# AJH_as3340_20.net
KiCad netlist of a schematic drawn in EAGLE
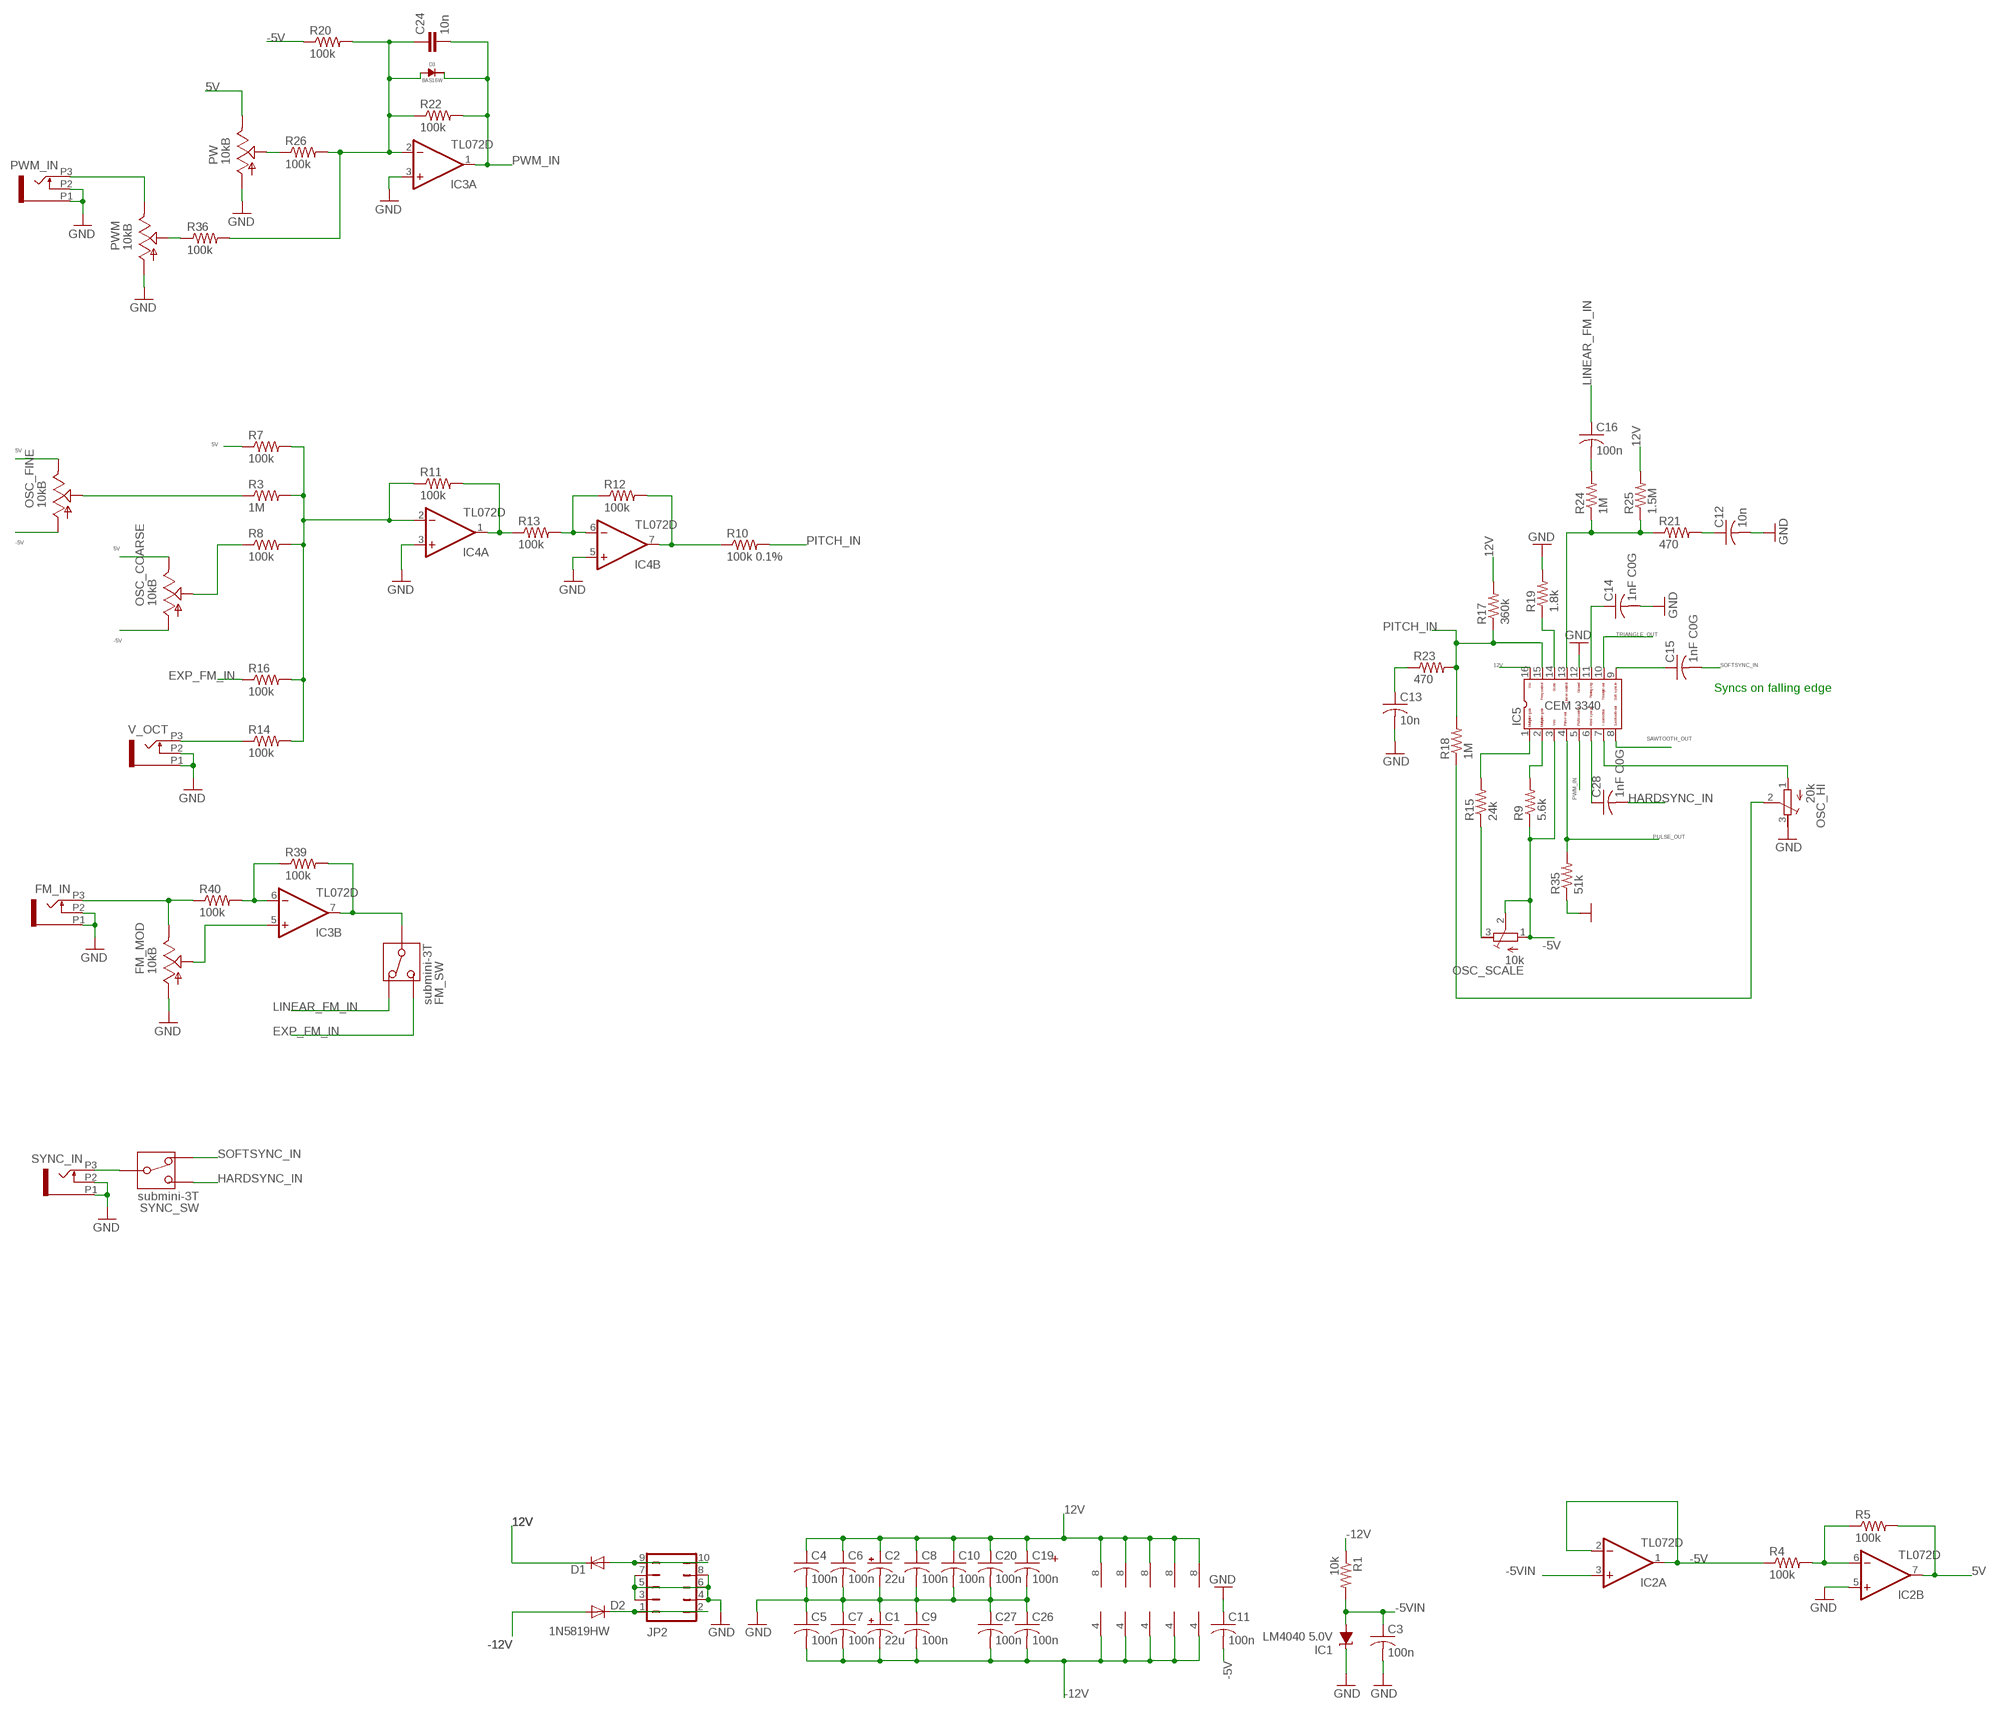
[diagram p0: schematic, sheet 1, part 1 of 2]
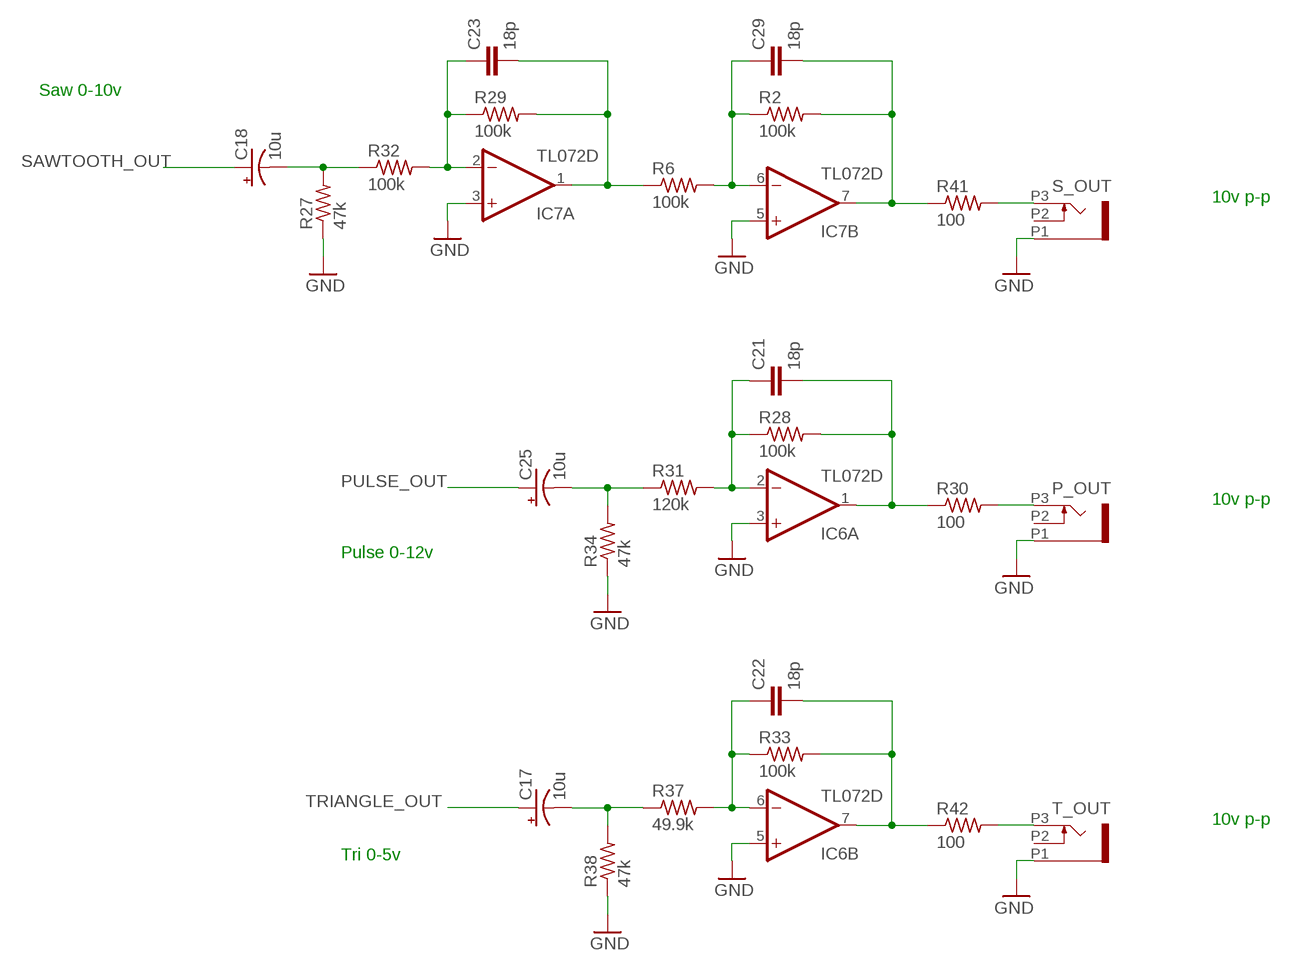
[diagram p1: schematic, sheet 1, part 2 of 2]

(export (version "E")
  (design (tool "Eeschema 10.0.6"))
  (components
    (comp (ref "C1")
      (value "22u")
      (footprint "eagle-import:PANASONIC_B")
      (libsource (lib "eagle-import") (part "CPOL-USB"))
    )
    (comp (ref "C2")
      (value "22u")
      (footprint "eagle-import:PANASONIC_B")
      (libsource (lib "eagle-import") (part "CPOL-USB"))
    )
    (comp (ref "C3")
      (value "100n")
      (footprint "eagle-import:C0603")
      (libsource (lib "eagle-import") (part "C-USC0603"))
    )
    (comp (ref "C4")
      (value "100n")
      (footprint "eagle-import:C0603")
      (libsource (lib "eagle-import") (part "C-USC0603"))
    )
    (comp (ref "C5")
      (value "100n")
      (footprint "eagle-import:C0603")
      (libsource (lib "eagle-import") (part "C-USC0603"))
    )
    (comp (ref "C6")
      (value "100n")
      (footprint "eagle-import:C0603")
      (libsource (lib "eagle-import") (part "C-USC0603"))
    )
    (comp (ref "C7")
      (value "100n")
      (footprint "eagle-import:C0603")
      (libsource (lib "eagle-import") (part "C-USC0603"))
    )
    (comp (ref "C8")
      (value "100n")
      (footprint "eagle-import:C0603")
      (libsource (lib "eagle-import") (part "C-USC0603"))
    )
    (comp (ref "C9")
      (value "100n")
      (footprint "eagle-import:C0603")
      (libsource (lib "eagle-import") (part "C-USC0603"))
    )
    (comp (ref "C10")
      (value "100n")
      (footprint "eagle-import:C0603")
      (libsource (lib "eagle-import") (part "C-USC0603"))
    )
    (comp (ref "C11")
      (value "100n")
      (footprint "eagle-import:C0603")
      (libsource (lib "eagle-import") (part "C-USC0603"))
    )
    (comp (ref "C12")
      (value "10n")
      (footprint "eagle-import:C0603")
      (libsource (lib "eagle-import") (part "C-USC0603"))
    )
    (comp (ref "C13")
      (value "10n")
      (footprint "eagle-import:C0603")
      (libsource (lib "eagle-import") (part "C-USC0603"))
    )
    (comp (ref "C14")
      (value "1nF C0G")
      (footprint "eagle-import:C0603")
      (libsource (lib "eagle-import") (part "C-USC0603"))
    )
    (comp (ref "C15")
      (value "1nF C0G")
      (footprint "eagle-import:C0603")
      (libsource (lib "eagle-import") (part "C-USC0603"))
    )
    (comp (ref "C16")
      (value "100n")
      (footprint "eagle-import:C0603")
      (libsource (lib "eagle-import") (part "C-USC0603"))
    )
    (comp (ref "C17")
      (value "10u")
      (footprint "eagle-import:PANASONIC_B")
      (libsource (lib "eagle-import") (part "CPOL-USB"))
    )
    (comp (ref "C18")
      (value "10u")
      (footprint "eagle-import:PANASONIC_B")
      (libsource (lib "eagle-import") (part "CPOL-USB"))
    )
    (comp (ref "C19")
      (value "100n")
      (footprint "eagle-import:C0603")
      (libsource (lib "eagle-import") (part "C-USC0603"))
    )
    (comp (ref "C20")
      (value "100n")
      (footprint "eagle-import:C0603")
      (libsource (lib "eagle-import") (part "C-USC0603"))
    )
    (comp (ref "C21")
      (value "18p")
      (footprint "eagle-import:C0603")
      (libsource (lib "eagle-import") (part "C-EUC0603"))
    )
    (comp (ref "C22")
      (value "18p")
      (footprint "eagle-import:C0603")
      (libsource (lib "eagle-import") (part "C-EUC0603"))
    )
    (comp (ref "C23")
      (value "18p")
      (footprint "eagle-import:C0603")
      (libsource (lib "eagle-import") (part "C-EUC0603"))
    )
    (comp (ref "C24")
      (value "10n")
      (footprint "eagle-import:C0603")
      (libsource (lib "eagle-import") (part "C-EUC0603"))
    )
    (comp (ref "C25")
      (value "10u")
      (footprint "eagle-import:PANASONIC_B")
      (libsource (lib "eagle-import") (part "CPOL-USB"))
    )
    (comp (ref "C26")
      (value "100n")
      (footprint "eagle-import:C0603")
      (libsource (lib "eagle-import") (part "C-USC0603"))
    )
    (comp (ref "C27")
      (value "100n")
      (footprint "eagle-import:C0603")
      (libsource (lib "eagle-import") (part "C-USC0603"))
    )
    (comp (ref "C28")
      (value "1nF C0G")
      (footprint "eagle-import:C0603")
      (libsource (lib "eagle-import") (part "C-USC0603"))
    )
    (comp (ref "C29")
      (value "18p")
      (footprint "eagle-import:C0603")
      (libsource (lib "eagle-import") (part "C-EUC0603"))
    )
    (comp (ref "D1")
      (value "1N5819HW")
      (footprint "eagle-import:SOD123")
      (libsource (lib "eagle-import") (part "DIODE-SOD123"))
    )
    (comp (ref "D2")
      (value "1N5819HW")
      (footprint "eagle-import:SOD123")
      (libsource (lib "eagle-import") (part "DIODE-SOD123"))
    )
    (comp (ref "D3")
      (value "BAS16W")
      (footprint "eagle-import:SOT-323")
      (libsource (lib "eagle-import") (part "BAS16W"))
    )
    (comp (ref "FM_IN")
      (value "PJ301_THONKICONN6")
      (footprint "eagle-import:WQP_PJ_301M6")
      (libsource (lib "eagle-import") (part "PJ301_THONKICONN6"))
    )
    (comp (ref "FM_MOD")
      (value "10kB")
      (footprint "eagle-import:ALPS_POT_VERTICAL_PS")
      (libsource (lib "eagle-import") (part "pot-alps_POT_USVERTICAL_PS"))
    )
    (comp (ref "FM_SW")
      (value "submini-3T")
      (footprint "eagle-import:SPDT-SUB")
      (libsource (lib "eagle-import") (part "SPDTT"))
    )
    (comp (ref "IC1")
      (value "LM4040 5.0V")
      (footprint "eagle-import:DBZ_R-PDSO-G3")
      (libsource (lib "eagle-import") (part "LM4041DBZC12"))
    )
    (comp (ref "IC2")
      (value "TL072D")
      (footprint "eagle-import:SO08")
      (libsource (lib "eagle-import") (part "TL072D"))
    )
    (comp (ref "IC3")
      (value "TL072D")
      (footprint "eagle-import:SO08")
      (libsource (lib "eagle-import") (part "TL072D"))
    )
    (comp (ref "IC4")
      (value "TL072D")
      (footprint "eagle-import:SO08")
      (libsource (lib "eagle-import") (part "TL072D"))
    )
    (comp (ref "IC5")
      (value "CEM3340SOIC16")
      (footprint "eagle-import:SO16")
      (libsource (lib "eagle-import") (part "CEM3340SOIC16"))
    )
    (comp (ref "IC6")
      (value "TL072D")
      (footprint "eagle-import:SO08")
      (libsource (lib "eagle-import") (part "TL072D"))
    )
    (comp (ref "IC7")
      (value "TL072D")
      (footprint "eagle-import:SO08")
      (libsource (lib "eagle-import") (part "TL072D"))
    )
    (comp (ref "JP2")
      (value "JP5Q")
      (footprint "eagle-import:JP5Q")
      (libsource (lib "eagle-import") (part "JP5Q"))
    )
    (comp (ref "OSC_COARSE")
      (value "10kB")
      (footprint "eagle-import:ALPS_POT_VERTICAL")
      (libsource (lib "eagle-import") (part "POT_USVERTICAL"))
    )
    (comp (ref "OSC_FINE")
      (value "10kB")
      (footprint "eagle-import:ALPS_POT_VERTICAL")
      (libsource (lib "eagle-import") (part "POT_USVERTICAL"))
    )
    (comp (ref "OSC_HI")
      (value "20k")
      (footprint "eagle-import:RTRIM3296X")
      (libsource (lib "eagle-import") (part "R-TRIMM3296X"))
    )
    (comp (ref "OSC_SCALE")
      (value "10k")
      (footprint "eagle-import:RTRIM3296X")
      (libsource (lib "eagle-import") (part "R-TRIMM3296X"))
    )
    (comp (ref "PW")
      (value "10kB")
      (footprint "eagle-import:ALPS_POT_VERTICAL_PS")
      (libsource (lib "eagle-import") (part "pot-alps_POT_USVERTICAL_PS"))
    )
    (comp (ref "PWM")
      (value "10kB")
      (footprint "eagle-import:ALPS_POT_VERTICAL_PS")
      (libsource (lib "eagle-import") (part "pot-alps_POT_USVERTICAL_PS"))
    )
    (comp (ref "PWM_IN")
      (value "PJ301_THONKICONN6")
      (footprint "eagle-import:WQP_PJ_301M6")
      (libsource (lib "eagle-import") (part "PJ301_THONKICONN6"))
    )
    (comp (ref "P_OUT")
      (value "PJ301_THONKICONN6")
      (footprint "eagle-import:WQP_PJ_301M6")
      (libsource (lib "eagle-import") (part "PJ301_THONKICONN6"))
    )
    (comp (ref "R1")
      (value "10k")
      (footprint "eagle-import:R0603")
      (libsource (lib "eagle-import") (part "R-US_R0603"))
    )
    (comp (ref "R2")
      (value "100k")
      (footprint "eagle-import:R0603")
      (libsource (lib "eagle-import") (part "R-US_R0603"))
    )
    (comp (ref "R3")
      (value "1M")
      (footprint "eagle-import:R0603")
      (libsource (lib "eagle-import") (part "R-US_R0603"))
    )
    (comp (ref "R4")
      (value "100k")
      (footprint "eagle-import:R0603")
      (libsource (lib "eagle-import") (part "R-US_R0603"))
    )
    (comp (ref "R5")
      (value "100k")
      (footprint "eagle-import:R0603")
      (libsource (lib "eagle-import") (part "R-US_R0603"))
    )
    (comp (ref "R6")
      (value "100k")
      (footprint "eagle-import:R0603")
      (libsource (lib "eagle-import") (part "R-US_R0603"))
    )
    (comp (ref "R7")
      (value "100k")
      (footprint "eagle-import:R0603")
      (libsource (lib "eagle-import") (part "R-US_R0603"))
    )
    (comp (ref "R8")
      (value "100k")
      (footprint "eagle-import:R0603")
      (libsource (lib "eagle-import") (part "R-US_R0603"))
    )
    (comp (ref "R9")
      (value "5.6k")
      (footprint "eagle-import:R0603")
      (libsource (lib "eagle-import") (part "R-US_R0603"))
    )
    (comp (ref "R10")
      (value "100k 0.1%")
      (footprint "eagle-import:R0603")
      (libsource (lib "eagle-import") (part "R-US_R0603"))
    )
    (comp (ref "R11")
      (value "100k")
      (footprint "eagle-import:R0603")
      (libsource (lib "eagle-import") (part "R-US_R0603"))
    )
    (comp (ref "R12")
      (value "100k")
      (footprint "eagle-import:R0603")
      (libsource (lib "eagle-import") (part "R-US_R0603"))
    )
    (comp (ref "R13")
      (value "100k")
      (footprint "eagle-import:R0603")
      (libsource (lib "eagle-import") (part "R-US_R0603"))
    )
    (comp (ref "R14")
      (value "100k")
      (footprint "eagle-import:R0603")
      (libsource (lib "eagle-import") (part "R-US_R0603"))
    )
    (comp (ref "R15")
      (value "24k")
      (footprint "eagle-import:R0603")
      (libsource (lib "eagle-import") (part "R-US_R0603"))
    )
    (comp (ref "R16")
      (value "100k")
      (footprint "eagle-import:R0603")
      (libsource (lib "eagle-import") (part "R-US_R0603"))
    )
    (comp (ref "R17")
      (value "360k")
      (footprint "eagle-import:R0603")
      (libsource (lib "eagle-import") (part "R-US_R0603"))
    )
    (comp (ref "R18")
      (value "1M")
      (footprint "eagle-import:R0603")
      (libsource (lib "eagle-import") (part "R-US_R0603"))
    )
    (comp (ref "R19")
      (value "1.8k")
      (footprint "eagle-import:R0603")
      (libsource (lib "eagle-import") (part "R-US_R0603"))
    )
    (comp (ref "R20")
      (value "100k")
      (footprint "eagle-import:R0603")
      (libsource (lib "eagle-import") (part "R-US_R0603"))
    )
    (comp (ref "R21")
      (value "470")
      (footprint "eagle-import:R0603")
      (libsource (lib "eagle-import") (part "R-US_R0603"))
    )
    (comp (ref "R22")
      (value "100k")
      (footprint "eagle-import:R0603")
      (libsource (lib "eagle-import") (part "R-US_R0603"))
    )
    (comp (ref "R23")
      (value "470")
      (footprint "eagle-import:R0603")
      (libsource (lib "eagle-import") (part "R-US_R0603"))
    )
    (comp (ref "R24")
      (value "1M")
      (footprint "eagle-import:R0603")
      (libsource (lib "eagle-import") (part "R-US_R0603"))
    )
    (comp (ref "R25")
      (value "1.5M")
      (footprint "eagle-import:R0603")
      (libsource (lib "eagle-import") (part "R-US_R0603"))
    )
    (comp (ref "R26")
      (value "100k")
      (footprint "eagle-import:R0603")
      (libsource (lib "eagle-import") (part "R-US_R0603"))
    )
    (comp (ref "R27")
      (value "47k")
      (footprint "eagle-import:R0603")
      (libsource (lib "eagle-import") (part "R-US_R0603"))
    )
    (comp (ref "R28")
      (value "100k")
      (footprint "eagle-import:R0603")
      (libsource (lib "eagle-import") (part "R-US_R0603"))
    )
    (comp (ref "R29")
      (value "100k")
      (footprint "eagle-import:R0603")
      (libsource (lib "eagle-import") (part "R-US_R0603"))
    )
    (comp (ref "R30")
      (value "100")
      (footprint "eagle-import:R0603")
      (libsource (lib "eagle-import") (part "R-US_R0603"))
    )
    (comp (ref "R31")
      (value "120k")
      (footprint "eagle-import:R0603")
      (libsource (lib "eagle-import") (part "R-US_R0603"))
    )
    (comp (ref "R32")
      (value "100k")
      (footprint "eagle-import:R0603")
      (libsource (lib "eagle-import") (part "R-US_R0603"))
    )
    (comp (ref "R33")
      (value "100k")
      (footprint "eagle-import:R0603")
      (libsource (lib "eagle-import") (part "R-US_R0603"))
    )
    (comp (ref "R34")
      (value "47k")
      (footprint "eagle-import:R0603")
      (libsource (lib "eagle-import") (part "R-US_R0603"))
    )
    (comp (ref "R35")
      (value "51k")
      (footprint "eagle-import:R0603")
      (libsource (lib "eagle-import") (part "R-US_R0603"))
    )
    (comp (ref "R36")
      (value "100k")
      (footprint "eagle-import:R0603")
      (libsource (lib "eagle-import") (part "R-US_R0603"))
    )
    (comp (ref "R37")
      (value "49.9k")
      (footprint "eagle-import:R0603")
      (libsource (lib "eagle-import") (part "R-US_R0603"))
    )
    (comp (ref "R38")
      (value "47k")
      (footprint "eagle-import:R0603")
      (libsource (lib "eagle-import") (part "R-US_R0603"))
    )
    (comp (ref "R39")
      (value "100k")
      (footprint "eagle-import:R0603")
      (libsource (lib "eagle-import") (part "R-US_R0603"))
    )
    (comp (ref "R40")
      (value "100k")
      (footprint "eagle-import:R0603")
      (libsource (lib "eagle-import") (part "R-US_R0603"))
    )
    (comp (ref "R41")
      (value "100")
      (footprint "eagle-import:R0603")
      (libsource (lib "eagle-import") (part "R-US_R0603"))
    )
    (comp (ref "R42")
      (value "100")
      (footprint "eagle-import:R0603")
      (libsource (lib "eagle-import") (part "R-US_R0603"))
    )
    (comp (ref "SYNC_IN")
      (value "PJ301_THONKICONN6")
      (footprint "eagle-import:WQP_PJ_301M6")
      (libsource (lib "eagle-import") (part "PJ301_THONKICONN6"))
    )
    (comp (ref "SYNC_SW")
      (value "submini-3T")
      (footprint "eagle-import:SPDT-SUB")
      (libsource (lib "eagle-import") (part "SPDTT"))
    )
    (comp (ref "S_OUT")
      (value "PJ301_THONKICONN6")
      (footprint "eagle-import:WQP_PJ_301M6")
      (libsource (lib "eagle-import") (part "PJ301_THONKICONN6"))
    )
    (comp (ref "T_OUT")
      (value "PJ301_THONKICONN6")
      (footprint "eagle-import:WQP_PJ_301M6")
      (libsource (lib "eagle-import") (part "PJ301_THONKICONN6"))
    )
    (comp (ref "V_OCT")
      (value "PJ301_THONKICONN6")
      (footprint "eagle-import:WQP_PJ_301M6")
      (libsource (lib "eagle-import") (part "PJ301_THONKICONN6"))
    )
  )
  (nets
    (net (code "1") (name "/-5V") (class "Default")
      (node (ref "C11") (pin "2") (pinfunction "2_2") (pintype "passive"))
      (node (ref "IC2") (pin "1") (pinfunction "OUT_1") (pintype "output"))
      (node (ref "IC2") (pin "2") (pinfunction "-IN_2") (pintype "input"))
      (node (ref "IC5") (pin "3") (pinfunction "3_3") (pintype "power_in"))
      (node (ref "OSC_COARSE") (pin "P$3") (pinfunction "A_P$3") (pintype "passive"))
      (node (ref "OSC_FINE") (pin "P$3") (pinfunction "A_P$3") (pintype "passive"))
      (node (ref "OSC_SCALE") (pin "1") (pinfunction "E_1") (pintype "passive"))
      (node (ref "OSC_SCALE") (pin "2") (pinfunction "S_2") (pintype "passive"))
      (node (ref "R20") (pin "1") (pinfunction "1_1") (pintype "passive"))
      (node (ref "R4") (pin "1") (pinfunction "1_1") (pintype "passive"))
      (node (ref "R9") (pin "1") (pinfunction "1_1") (pintype "passive"))
    )
    (net (code "2") (name "/-5VIN") (class "Default")
      (node (ref "C3") (pin "1") (pinfunction "1_1") (pintype "passive"))
      (node (ref "IC1") (pin "2") (pinfunction "A_2") (pintype "passive"))
      (node (ref "IC2") (pin "3") (pinfunction "+IN_3") (pintype "input"))
      (node (ref "R1") (pin "2") (pinfunction "2_2") (pintype "passive"))
    )
    (net (code "3") (name "/-12V") (class "Default")
      (node (ref "C1") (pin "-") (pinfunction "-_-") (pintype "passive"))
      (node (ref "C26") (pin "2") (pinfunction "2_2") (pintype "passive"))
      (node (ref "C27") (pin "2") (pinfunction "2_2") (pintype "passive"))
      (node (ref "C5") (pin "2") (pinfunction "2_2") (pintype "passive"))
      (node (ref "C7") (pin "2") (pinfunction "2_2") (pintype "passive"))
      (node (ref "C9") (pin "2") (pinfunction "2_2") (pintype "passive"))
      (node (ref "D2") (pin "A") (pinfunction "A_A") (pintype "passive"))
      (node (ref "IC2") (pin "4") (pinfunction "V-_4") (pintype "power_in"))
      (node (ref "IC3") (pin "4") (pinfunction "V-_4") (pintype "power_in"))
      (node (ref "IC4") (pin "4") (pinfunction "V-_4") (pintype "power_in"))
      (node (ref "IC6") (pin "4") (pinfunction "V-_4") (pintype "power_in"))
      (node (ref "IC7") (pin "4") (pinfunction "V-_4") (pintype "power_in"))
      (node (ref "R1") (pin "1") (pinfunction "1_1") (pintype "passive"))
    )
    (net (code "4") (name "/5V") (class "Default")
      (node (ref "IC2") (pin "7") (pinfunction "OUT_7") (pintype "output"))
      (node (ref "OSC_COARSE") (pin "P$1") (pinfunction "E_P$1") (pintype "passive"))
      (node (ref "OSC_FINE") (pin "P$1") (pinfunction "E_P$1") (pintype "passive"))
      (node (ref "PW") (pin "P$1") (pinfunction "E_P$1") (pintype "passive"))
      (node (ref "R5") (pin "2") (pinfunction "2_2") (pintype "passive"))
      (node (ref "R7") (pin "1") (pinfunction "1_1") (pintype "passive"))
    )
    (net (code "5") (name "/12V") (class "Default")
      (node (ref "C10") (pin "1") (pinfunction "1_1") (pintype "passive"))
      (node (ref "C19") (pin "1") (pinfunction "1_1") (pintype "passive"))
      (node (ref "C2") (pin "+") (pinfunction "+_+") (pintype "passive"))
      (node (ref "C20") (pin "1") (pinfunction "1_1") (pintype "passive"))
      (node (ref "C4") (pin "1") (pinfunction "1_1") (pintype "passive"))
      (node (ref "C6") (pin "1") (pinfunction "1_1") (pintype "passive"))
      (node (ref "C8") (pin "1") (pinfunction "1_1") (pintype "passive"))
      (node (ref "D1") (pin "C") (pinfunction "C_C") (pintype "passive"))
      (node (ref "IC2") (pin "8") (pinfunction "V+_8") (pintype "power_in"))
      (node (ref "IC3") (pin "8") (pinfunction "V+_8") (pintype "power_in"))
      (node (ref "IC4") (pin "8") (pinfunction "V+_8") (pintype "power_in"))
      (node (ref "IC5") (pin "16") (pinfunction "16_16") (pintype "power_in"))
      (node (ref "IC6") (pin "8") (pinfunction "V+_8") (pintype "power_in"))
      (node (ref "IC7") (pin "8") (pinfunction "V+_8") (pintype "power_in"))
      (node (ref "R17") (pin "2") (pinfunction "2_2") (pintype "passive"))
      (node (ref "R25") (pin "2") (pinfunction "2_2") (pintype "passive"))
    )
    (net (code "6") (name "/EXP_FM_IN") (class "Default")
      (node (ref "FM_SW") (pin "P$1") (pinfunction "P$1_P$1") (pintype "passive"))
      (node (ref "R16") (pin "1") (pinfunction "1_1") (pintype "passive"))
    )
    (net (code "7") (name "/HARDSYNC_IN") (class "Default")
      (node (ref "C28") (pin "2") (pinfunction "2_2") (pintype "passive"))
      (node (ref "SYNC_SW") (pin "P$1") (pinfunction "P$1_P$1") (pintype "passive"))
    )
    (net (code "8") (name "/LINEAR_FM_IN") (class "Default")
      (node (ref "C16") (pin "1") (pinfunction "1_1") (pintype "passive"))
      (node (ref "FM_SW") (pin "P$3") (pinfunction "P$3_P$3") (pintype "passive"))
    )
    (net (code "9") (name "/PITCH_IN") (class "Default")
      (node (ref "IC5") (pin "15") (pinfunction "15_15") (pintype "input"))
      (node (ref "R10") (pin "2") (pinfunction "2_2") (pintype "passive"))
      (node (ref "R17") (pin "1") (pinfunction "1_1") (pintype "passive"))
      (node (ref "R18") (pin "2") (pinfunction "2_2") (pintype "passive"))
      (node (ref "R23") (pin "2") (pinfunction "2_2") (pintype "passive"))
    )
    (net (code "10") (name "/PULSE_OUT") (class "Default")
      (node (ref "C25") (pin "+") (pinfunction "+_+") (pintype "passive"))
      (node (ref "IC5") (pin "4") (pinfunction "4_4") (pintype "output"))
      (node (ref "R35") (pin "2") (pinfunction "2_2") (pintype "passive"))
    )
    (net (code "11") (name "/PWM_IN") (class "Default")
      (node (ref "C24") (pin "2") (pinfunction "2_2") (pintype "passive"))
      (node (ref "D3") (pin "CATHODE") (pinfunction "CATHODE_CATHODE") (pintype "bidirectional"))
      (node (ref "IC3") (pin "1") (pinfunction "OUT_1") (pintype "output"))
      (node (ref "IC5") (pin "5") (pinfunction "5_5") (pintype "input"))
      (node (ref "R22") (pin "2") (pinfunction "2_2") (pintype "passive"))
    )
    (net (code "12") (name "/SAWTOOTH_OUT") (class "Default")
      (node (ref "C18") (pin "+") (pinfunction "+_+") (pintype "passive"))
      (node (ref "IC5") (pin "8") (pinfunction "8_8") (pintype "output"))
    )
    (net (code "13") (name "/SOFTSYNC_IN") (class "Default")
      (node (ref "C15") (pin "2") (pinfunction "2_2") (pintype "passive"))
      (node (ref "SYNC_SW") (pin "P$3") (pinfunction "P$3_P$3") (pintype "passive"))
    )
    (net (code "14") (name "/TRIANGLE_OUT") (class "Default")
      (node (ref "C17") (pin "+") (pinfunction "+_+") (pintype "passive"))
      (node (ref "IC5") (pin "10") (pinfunction "10_10") (pintype "output"))
    )
    (net (code "15") (name "GND") (class "Default")
      (node (ref "C1") (pin "+") (pinfunction "+_+") (pintype "passive"))
      (node (ref "C10") (pin "2") (pinfunction "2_2") (pintype "passive"))
      (node (ref "C11") (pin "1") (pinfunction "1_1") (pintype "passive"))
      (node (ref "C12") (pin "2") (pinfunction "2_2") (pintype "passive"))
      (node (ref "C13") (pin "2") (pinfunction "2_2") (pintype "passive"))
      (node (ref "C14") (pin "2") (pinfunction "2_2") (pintype "passive"))
      (node (ref "C19") (pin "2") (pinfunction "2_2") (pintype "passive"))
      (node (ref "C2") (pin "-") (pinfunction "-_-") (pintype "passive"))
      (node (ref "C20") (pin "2") (pinfunction "2_2") (pintype "passive"))
      (node (ref "C26") (pin "1") (pinfunction "1_1") (pintype "passive"))
      (node (ref "C27") (pin "1") (pinfunction "1_1") (pintype "passive"))
      (node (ref "C3") (pin "2") (pinfunction "2_2") (pintype "passive"))
      (node (ref "C4") (pin "2") (pinfunction "2_2") (pintype "passive"))
      (node (ref "C5") (pin "1") (pinfunction "1_1") (pintype "passive"))
      (node (ref "C6") (pin "2") (pinfunction "2_2") (pintype "passive"))
      (node (ref "C7") (pin "1") (pinfunction "1_1") (pintype "passive"))
      (node (ref "C8") (pin "2") (pinfunction "2_2") (pintype "passive"))
      (node (ref "C9") (pin "1") (pinfunction "1_1") (pintype "passive"))
      (node (ref "FM_IN") (pin "P1") (pinfunction "1_P1") (pintype "passive"))
      (node (ref "FM_IN") (pin "P2") (pinfunction "2_P2") (pintype "passive"))
      (node (ref "FM_MOD") (pin "P$3") (pinfunction "A_P$3") (pintype "passive"))
      (node (ref "IC1") (pin "1") (pinfunction "C_1") (pintype "passive"))
      (node (ref "IC2") (pin "5") (pinfunction "+IN_5") (pintype "input"))
      (node (ref "IC3") (pin "3") (pinfunction "+IN_3") (pintype "input"))
      (node (ref "IC4") (pin "3") (pinfunction "+IN_3") (pintype "input"))
      (node (ref "IC4") (pin "5") (pinfunction "+IN_5") (pintype "input"))
      (node (ref "IC5") (pin "12") (pinfunction "12_12") (pintype "power_in"))
      (node (ref "IC6") (pin "3") (pinfunction "+IN_3") (pintype "input"))
      (node (ref "IC6") (pin "5") (pinfunction "+IN_5") (pintype "input"))
      (node (ref "IC7") (pin "3") (pinfunction "+IN_3") (pintype "input"))
      (node (ref "IC7") (pin "5") (pinfunction "+IN_5") (pintype "input"))
      (node (ref "JP2") (pin "3") (pinfunction "3_3") (pintype "passive"))
      (node (ref "JP2") (pin "4") (pinfunction "4_4") (pintype "passive"))
      (node (ref "JP2") (pin "5") (pinfunction "5_5") (pintype "passive"))
      (node (ref "JP2") (pin "6") (pinfunction "6_6") (pintype "passive"))
      (node (ref "JP2") (pin "7") (pinfunction "7_7") (pintype "passive"))
      (node (ref "JP2") (pin "8") (pinfunction "8_8") (pintype "passive"))
      (node (ref "OSC_HI") (pin "3") (pinfunction "A_3") (pintype "passive"))
      (node (ref "PW") (pin "P$3") (pinfunction "A_P$3") (pintype "passive"))
      (node (ref "PWM") (pin "P$3") (pinfunction "A_P$3") (pintype "passive"))
      (node (ref "PWM_IN") (pin "P1") (pinfunction "1_P1") (pintype "passive"))
      (node (ref "PWM_IN") (pin "P2") (pinfunction "2_P2") (pintype "passive"))
      (node (ref "P_OUT") (pin "P1") (pinfunction "1_P1") (pintype "passive"))
      (node (ref "R19") (pin "2") (pinfunction "2_2") (pintype "passive"))
      (node (ref "R27") (pin "1") (pinfunction "1_1") (pintype "passive"))
      (node (ref "R34") (pin "1") (pinfunction "1_1") (pintype "passive"))
      (node (ref "R35") (pin "1") (pinfunction "1_1") (pintype "passive"))
      (node (ref "R38") (pin "1") (pinfunction "1_1") (pintype "passive"))
      (node (ref "SYNC_IN") (pin "P1") (pinfunction "1_P1") (pintype "passive"))
      (node (ref "SYNC_IN") (pin "P2") (pinfunction "2_P2") (pintype "passive"))
      (node (ref "S_OUT") (pin "P1") (pinfunction "1_P1") (pintype "passive"))
      (node (ref "T_OUT") (pin "P1") (pinfunction "1_P1") (pintype "passive"))
      (node (ref "V_OCT") (pin "P1") (pinfunction "1_P1") (pintype "passive"))
      (node (ref "V_OCT") (pin "P2") (pinfunction "2_P2") (pintype "passive"))
    )
    (net (code "16") (name "Net-(C12-Pad1)") (class "Default")
      (node (ref "C12") (pin "1") (pinfunction "1_1") (pintype "passive"))
      (node (ref "R21") (pin "2") (pinfunction "2_2") (pintype "passive"))
    )
    (net (code "17") (name "Net-(C13-Pad1)") (class "Default")
      (node (ref "C13") (pin "1") (pinfunction "1_1") (pintype "passive"))
      (node (ref "R23") (pin "1") (pinfunction "1_1") (pintype "passive"))
    )
    (net (code "18") (name "Net-(C14-Pad1)") (class "Default")
      (node (ref "C14") (pin "1") (pinfunction "1_1") (pintype "passive"))
      (node (ref "IC5") (pin "11") (pinfunction "11_11") (pintype "bidirectional"))
    )
    (net (code "19") (name "Net-(C15-Pad1)") (class "Default")
      (node (ref "C15") (pin "1") (pinfunction "1_1") (pintype "passive"))
      (node (ref "IC5") (pin "9") (pinfunction "9_9") (pintype "input"))
    )
    (net (code "20") (name "Net-(C16-Pad2)") (class "Default")
      (node (ref "C16") (pin "2") (pinfunction "2_2") (pintype "passive"))
      (node (ref "R24") (pin "2") (pinfunction "2_2") (pintype "passive"))
    )
    (net (code "21") (name "Net-(C17-Pad-)") (class "Default")
      (node (ref "C17") (pin "-") (pinfunction "-_-") (pintype "passive"))
      (node (ref "R37") (pin "1") (pinfunction "1_1") (pintype "passive"))
      (node (ref "R38") (pin "2") (pinfunction "2_2") (pintype "passive"))
    )
    (net (code "22") (name "Net-(C18-Pad-)") (class "Default")
      (node (ref "C18") (pin "-") (pinfunction "-_-") (pintype "passive"))
      (node (ref "R27") (pin "2") (pinfunction "2_2") (pintype "passive"))
      (node (ref "R32") (pin "1") (pinfunction "1_1") (pintype "passive"))
    )
    (net (code "23") (name "Net-(C25-Pad-)") (class "Default")
      (node (ref "C25") (pin "-") (pinfunction "-_-") (pintype "passive"))
      (node (ref "R31") (pin "1") (pinfunction "1_1") (pintype "passive"))
      (node (ref "R34") (pin "2") (pinfunction "2_2") (pintype "passive"))
    )
    (net (code "24") (name "Net-(C28-Pad1)") (class "Default")
      (node (ref "C28") (pin "1") (pinfunction "1_1") (pintype "passive"))
      (node (ref "IC5") (pin "6") (pinfunction "6_6") (pintype "input"))
    )
    (net (code "25") (name "Net-(D1-PadA)") (class "Default")
      (node (ref "D1") (pin "A") (pinfunction "A_A") (pintype "passive"))
      (node (ref "JP2") (pin "10") (pinfunction "10_10") (pintype "passive"))
      (node (ref "JP2") (pin "9") (pinfunction "9_9") (pintype "passive"))
    )
    (net (code "26") (name "Net-(D2-PadC)") (class "Default")
      (node (ref "D2") (pin "C") (pinfunction "C_C") (pintype "passive"))
      (node (ref "JP2") (pin "1") (pinfunction "1_1") (pintype "passive"))
      (node (ref "JP2") (pin "2") (pinfunction "2_2") (pintype "passive"))
    )
    (net (code "27") (name "Net-(FM_IN-3)") (class "Default")
      (node (ref "FM_IN") (pin "P3") (pinfunction "3_P3") (pintype "passive"))
      (node (ref "FM_MOD") (pin "P$1") (pinfunction "E_P$1") (pintype "passive"))
      (node (ref "R40") (pin "1") (pinfunction "1_1") (pintype "passive"))
    )
    (net (code "28") (name "Net-(FM_MOD-S)") (class "Default")
      (node (ref "FM_MOD") (pin "P$2") (pinfunction "S_P$2") (pintype "passive"))
      (node (ref "IC3") (pin "5") (pinfunction "+IN_5") (pintype "input"))
    )
    (net (code "29") (name "Net-(IC2B--IN)") (class "Default")
      (node (ref "IC2") (pin "6") (pinfunction "-IN_6") (pintype "input"))
      (node (ref "R4") (pin "2") (pinfunction "2_2") (pintype "passive"))
      (node (ref "R5") (pin "1") (pinfunction "1_1") (pintype "passive"))
    )
    (net (code "30") (name "Net-(IC3A--IN)") (class "Default")
      (node (ref "C24") (pin "1") (pinfunction "1_1") (pintype "passive"))
      (node (ref "D3") (pin "ANODE") (pinfunction "ANODE_ANODE") (pintype "bidirectional"))
      (node (ref "IC3") (pin "2") (pinfunction "-IN_2") (pintype "input"))
      (node (ref "R20") (pin "2") (pinfunction "2_2") (pintype "passive"))
      (node (ref "R22") (pin "1") (pinfunction "1_1") (pintype "passive"))
      (node (ref "R26") (pin "2") (pinfunction "2_2") (pintype "passive"))
      (node (ref "R36") (pin "2") (pinfunction "2_2") (pintype "passive"))
    )
    (net (code "31") (name "Net-(IC3B--IN)") (class "Default")
      (node (ref "IC3") (pin "6") (pinfunction "-IN_6") (pintype "input"))
      (node (ref "R39") (pin "1") (pinfunction "1_1") (pintype "passive"))
      (node (ref "R40") (pin "2") (pinfunction "2_2") (pintype "passive"))
    )
    (net (code "32") (name "Net-(IC3B-OUT)") (class "Default")
      (node (ref "FM_SW") (pin "P$2") (pinfunction "P$2_P$2") (pintype "passive"))
      (node (ref "IC3") (pin "7") (pinfunction "OUT_7") (pintype "output"))
      (node (ref "R39") (pin "2") (pinfunction "2_2") (pintype "passive"))
    )
    (net (code "33") (name "Net-(IC4A--IN)") (class "Default")
      (node (ref "IC4") (pin "2") (pinfunction "-IN_2") (pintype "input"))
      (node (ref "R11") (pin "1") (pinfunction "1_1") (pintype "passive"))
      (node (ref "R14") (pin "2") (pinfunction "2_2") (pintype "passive"))
      (node (ref "R16") (pin "2") (pinfunction "2_2") (pintype "passive"))
      (node (ref "R3") (pin "2") (pinfunction "2_2") (pintype "passive"))
      (node (ref "R7") (pin "2") (pinfunction "2_2") (pintype "passive"))
      (node (ref "R8") (pin "2") (pinfunction "2_2") (pintype "passive"))
    )
    (net (code "34") (name "Net-(IC4A-OUT)") (class "Default")
      (node (ref "IC4") (pin "1") (pinfunction "OUT_1") (pintype "output"))
      (node (ref "R11") (pin "2") (pinfunction "2_2") (pintype "passive"))
      (node (ref "R13") (pin "1") (pinfunction "1_1") (pintype "passive"))
    )
    (net (code "35") (name "Net-(IC4B--IN)") (class "Default")
      (node (ref "IC4") (pin "6") (pinfunction "-IN_6") (pintype "input"))
      (node (ref "R12") (pin "1") (pinfunction "1_1") (pintype "passive"))
      (node (ref "R13") (pin "2") (pinfunction "2_2") (pintype "passive"))
    )
    (net (code "36") (name "Net-(IC4B-OUT)") (class "Default")
      (node (ref "IC4") (pin "7") (pinfunction "OUT_7") (pintype "output"))
      (node (ref "R10") (pin "1") (pinfunction "1_1") (pintype "passive"))
      (node (ref "R12") (pin "2") (pinfunction "2_2") (pintype "passive"))
    )
    (net (code "37") (name "Net-(IC5-Pad1)") (class "Default")
      (node (ref "IC5") (pin "1") (pinfunction "1_1") (pintype "bidirectional"))
      (node (ref "R15") (pin "2") (pinfunction "2_2") (pintype "passive"))
    )
    (net (code "38") (name "Net-(IC5-Pad2)") (class "Default")
      (node (ref "IC5") (pin "2") (pinfunction "2_2") (pintype "bidirectional"))
      (node (ref "R9") (pin "2") (pinfunction "2_2") (pintype "passive"))
    )
    (net (code "39") (name "Net-(IC5-Pad13)") (class "Default")
      (node (ref "IC5") (pin "13") (pinfunction "13_13") (pintype "input"))
      (node (ref "R21") (pin "1") (pinfunction "1_1") (pintype "passive"))
      (node (ref "R24") (pin "1") (pinfunction "1_1") (pintype "passive"))
      (node (ref "R25") (pin "1") (pinfunction "1_1") (pintype "passive"))
    )
    (net (code "40") (name "Net-(IC5-Pad14)") (class "Default")
      (node (ref "IC5") (pin "14") (pinfunction "14_14") (pintype "input"))
      (node (ref "R19") (pin "1") (pinfunction "1_1") (pintype "passive"))
    )
    (net (code "41") (name "Net-(IC6A--IN)") (class "Default")
      (node (ref "C21") (pin "1") (pinfunction "1_1") (pintype "passive"))
      (node (ref "IC6") (pin "2") (pinfunction "-IN_2") (pintype "input"))
      (node (ref "R28") (pin "1") (pinfunction "1_1") (pintype "passive"))
      (node (ref "R31") (pin "2") (pinfunction "2_2") (pintype "passive"))
    )
    (net (code "42") (name "Net-(IC6A-OUT)") (class "Default")
      (node (ref "C21") (pin "2") (pinfunction "2_2") (pintype "passive"))
      (node (ref "IC6") (pin "1") (pinfunction "OUT_1") (pintype "output"))
      (node (ref "R28") (pin "2") (pinfunction "2_2") (pintype "passive"))
      (node (ref "R30") (pin "1") (pinfunction "1_1") (pintype "passive"))
    )
    (net (code "43") (name "Net-(IC6B--IN)") (class "Default")
      (node (ref "C22") (pin "1") (pinfunction "1_1") (pintype "passive"))
      (node (ref "IC6") (pin "6") (pinfunction "-IN_6") (pintype "input"))
      (node (ref "R33") (pin "1") (pinfunction "1_1") (pintype "passive"))
      (node (ref "R37") (pin "2") (pinfunction "2_2") (pintype "passive"))
    )
    (net (code "44") (name "Net-(IC6B-OUT)") (class "Default")
      (node (ref "C22") (pin "2") (pinfunction "2_2") (pintype "passive"))
      (node (ref "IC6") (pin "7") (pinfunction "OUT_7") (pintype "output"))
      (node (ref "R33") (pin "2") (pinfunction "2_2") (pintype "passive"))
      (node (ref "R42") (pin "1") (pinfunction "1_1") (pintype "passive"))
    )
    (net (code "45") (name "Net-(IC7A--IN)") (class "Default")
      (node (ref "C23") (pin "1") (pinfunction "1_1") (pintype "passive"))
      (node (ref "IC7") (pin "2") (pinfunction "-IN_2") (pintype "input"))
      (node (ref "R29") (pin "1") (pinfunction "1_1") (pintype "passive"))
      (node (ref "R32") (pin "2") (pinfunction "2_2") (pintype "passive"))
    )
    (net (code "46") (name "Net-(IC7A-OUT)") (class "Default")
      (node (ref "C23") (pin "2") (pinfunction "2_2") (pintype "passive"))
      (node (ref "IC7") (pin "1") (pinfunction "OUT_1") (pintype "output"))
      (node (ref "R29") (pin "2") (pinfunction "2_2") (pintype "passive"))
      (node (ref "R6") (pin "1") (pinfunction "1_1") (pintype "passive"))
    )
    (net (code "47") (name "Net-(IC7B--IN)") (class "Default")
      (node (ref "C29") (pin "1") (pinfunction "1_1") (pintype "passive"))
      (node (ref "IC7") (pin "6") (pinfunction "-IN_6") (pintype "input"))
      (node (ref "R2") (pin "1") (pinfunction "1_1") (pintype "passive"))
      (node (ref "R6") (pin "2") (pinfunction "2_2") (pintype "passive"))
    )
    (net (code "48") (name "Net-(IC7B-OUT)") (class "Default")
      (node (ref "C29") (pin "2") (pinfunction "2_2") (pintype "passive"))
      (node (ref "IC7") (pin "7") (pinfunction "OUT_7") (pintype "output"))
      (node (ref "R2") (pin "2") (pinfunction "2_2") (pintype "passive"))
      (node (ref "R41") (pin "1") (pinfunction "1_1") (pintype "passive"))
    )
    (net (code "49") (name "Net-(OSC_COARSE-S)") (class "Default")
      (node (ref "OSC_COARSE") (pin "P$2") (pinfunction "S_P$2") (pintype "passive"))
      (node (ref "R8") (pin "1") (pinfunction "1_1") (pintype "passive"))
    )
    (net (code "50") (name "Net-(OSC_FINE-S)") (class "Default")
      (node (ref "OSC_FINE") (pin "P$2") (pinfunction "S_P$2") (pintype "passive"))
      (node (ref "R3") (pin "1") (pinfunction "1_1") (pintype "passive"))
    )
    (net (code "51") (name "Net-(OSC_HI-E)") (class "Default")
      (node (ref "IC5") (pin "7") (pinfunction "7_7") (pintype "bidirectional"))
      (node (ref "OSC_HI") (pin "1") (pinfunction "E_1") (pintype "passive"))
    )
    (net (code "52") (name "Net-(OSC_HI-S)") (class "Default")
      (node (ref "OSC_HI") (pin "2") (pinfunction "S_2") (pintype "passive"))
      (node (ref "R18") (pin "1") (pinfunction "1_1") (pintype "passive"))
    )
    (net (code "53") (name "Net-(OSC_SCALE-A)") (class "Default")
      (node (ref "OSC_SCALE") (pin "3") (pinfunction "A_3") (pintype "passive"))
      (node (ref "R15") (pin "1") (pinfunction "1_1") (pintype "passive"))
    )
    (net (code "54") (name "Net-(PW-S)") (class "Default")
      (node (ref "PW") (pin "P$2") (pinfunction "S_P$2") (pintype "passive"))
      (node (ref "R26") (pin "1") (pinfunction "1_1") (pintype "passive"))
    )
    (net (code "55") (name "Net-(PWM-E)") (class "Default")
      (node (ref "PWM") (pin "P$1") (pinfunction "E_P$1") (pintype "passive"))
      (node (ref "PWM_IN") (pin "P3") (pinfunction "3_P3") (pintype "passive"))
    )
    (net (code "56") (name "Net-(PWM-S)") (class "Default")
      (node (ref "PWM") (pin "P$2") (pinfunction "S_P$2") (pintype "passive"))
      (node (ref "R36") (pin "1") (pinfunction "1_1") (pintype "passive"))
    )
    (net (code "57") (name "Net-(P_OUT-3)") (class "Default")
      (node (ref "P_OUT") (pin "P3") (pinfunction "3_P3") (pintype "passive"))
      (node (ref "R30") (pin "2") (pinfunction "2_2") (pintype "passive"))
    )
    (net (code "58") (name "Net-(SYNC_IN-3)") (class "Default")
      (node (ref "SYNC_IN") (pin "P3") (pinfunction "3_P3") (pintype "passive"))
      (node (ref "SYNC_SW") (pin "P$2") (pinfunction "P$2_P$2") (pintype "passive"))
    )
    (net (code "59") (name "Net-(S_OUT-3)") (class "Default")
      (node (ref "R41") (pin "2") (pinfunction "2_2") (pintype "passive"))
      (node (ref "S_OUT") (pin "P3") (pinfunction "3_P3") (pintype "passive"))
    )
    (net (code "60") (name "Net-(T_OUT-3)") (class "Default")
      (node (ref "R42") (pin "2") (pinfunction "2_2") (pintype "passive"))
      (node (ref "T_OUT") (pin "P3") (pinfunction "3_P3") (pintype "passive"))
    )
    (net (code "61") (name "Net-(V_OCT-3)") (class "Default")
      (node (ref "R14") (pin "1") (pinfunction "1_1") (pintype "passive"))
      (node (ref "V_OCT") (pin "P3") (pinfunction "3_P3") (pintype "passive"))
    )
    (net (code "62") (name "unconnected-(P_OUT-2-PadP2)") (class "Default")
      (node (ref "P_OUT") (pin "P2") (pinfunction "2_P2") (pintype "passive"))
    )
    (net (code "63") (name "unconnected-(S_OUT-2-PadP2)") (class "Default")
      (node (ref "S_OUT") (pin "P2") (pinfunction "2_P2") (pintype "passive"))
    )
    (net (code "64") (name "unconnected-(T_OUT-2-PadP2)") (class "Default")
      (node (ref "T_OUT") (pin "P2") (pinfunction "2_P2") (pintype "passive"))
    )
  )
)
